# ATmega328.net
KiCad netlist of a schematic drawn in EAGLE
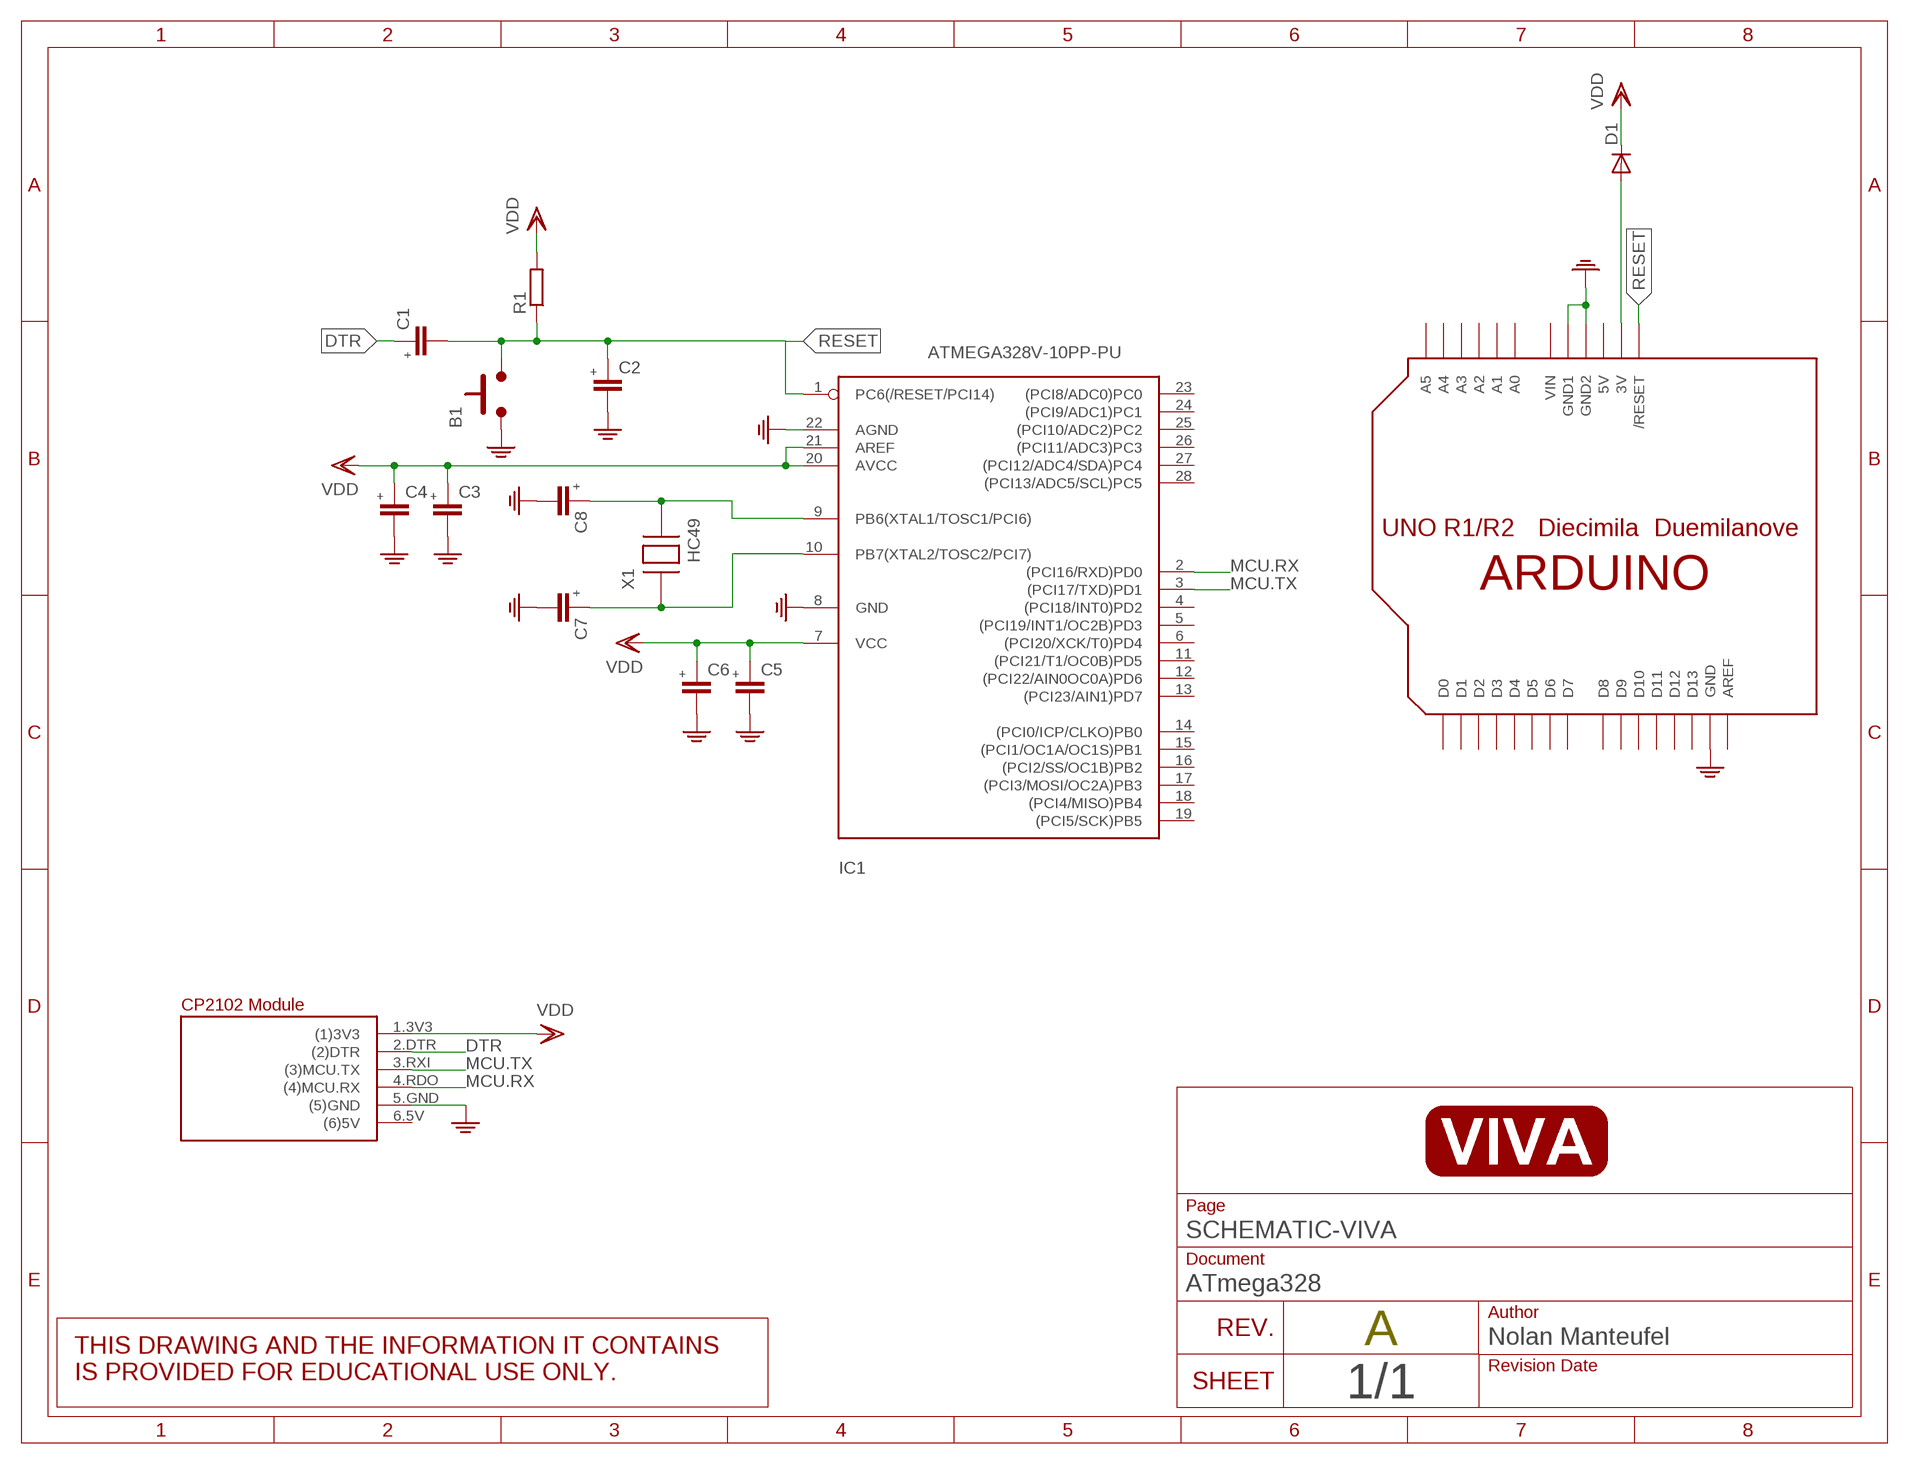
[diagram p0: schematic, sheet 1]

(export (version "E")
  (design (tool "Eeschema 10.0.6"))
  (components
    (comp (ref "B1")
      (value "PUSHBUTTON6X6MM")
      (footprint "eagle-import:6X6MM")
      (libsource (lib "eagle-import") (part "PUSHBUTTON6X6MM"))
    )
    (comp (ref "C1")
      (value "C-EUC0805")
      (footprint "eagle-import:C0805")
      (libsource (lib "eagle-import") (part "C-EUC0805"))
    )
    (comp (ref "C2")
      (value "C-EUC0805")
      (footprint "eagle-import:C0805")
      (libsource (lib "eagle-import") (part "C-EUC0805"))
    )
    (comp (ref "C3")
      (value "C-EUC0805")
      (footprint "eagle-import:C0805")
      (libsource (lib "eagle-import") (part "C-EUC0805"))
    )
    (comp (ref "C4")
      (value "C-EUC0805")
      (footprint "eagle-import:C0805")
      (libsource (lib "eagle-import") (part "C-EUC0805"))
    )
    (comp (ref "C5")
      (value "C-EUC0805")
      (footprint "eagle-import:C0805")
      (libsource (lib "eagle-import") (part "C-EUC0805"))
    )
    (comp (ref "C6")
      (value "C-EUC0805")
      (footprint "eagle-import:C0805")
      (libsource (lib "eagle-import") (part "C-EUC0805"))
    )
    (comp (ref "C7")
      (value "C-EUC0805")
      (footprint "eagle-import:C0805")
      (libsource (lib "eagle-import") (part "C-EUC0805"))
    )
    (comp (ref "C8")
      (value "C-EUC0805")
      (footprint "eagle-import:C0805")
      (libsource (lib "eagle-import") (part "C-EUC0805"))
    )
    (comp (ref "D1")
      (value "DIODE-SOD123")
      (footprint "eagle-import:SOD123")
      (libsource (lib "eagle-import") (part "DIODE-SOD123"))
    )
    (comp (ref "IC1")
      (value "ATMEGA328V-10PP-PU")
      (footprint "eagle-import:DIL28-3")
      (libsource (lib "eagle-import") (part "ATMEGA328PP-PUV-10"))
    )
    (comp (ref "R1")
      (value "R-EU_R0805")
      (footprint "eagle-import:R0805")
      (libsource (lib "eagle-import") (part "R-EU_R0805"))
    )
    (comp (ref "U$2")
      (value "ARDUINOUNO")
      (footprint "eagle-import:ARDUINO")
      (libsource (lib "eagle-import") (part "ARDUINOUNO"))
    )
    (comp (ref "U$3")
      (value "VIVA_USB-TTLTEXT")
      (footprint "eagle-import:VIVA_USB-TTL")
      (libsource (lib "eagle-import") (part "VIVA_USB-TTLTEXT"))
    )
    (comp (ref "X1")
      (value "HC49")
      (footprint "eagle-import:HC49S")
      (libsource (lib "eagle-import") (part "CRYSTAL-M"))
    )
  )
  (nets
    (net (code "1") (name "/5V") (class "Default")
      (node (ref "U$2") (pin "5V") (pinfunction "5V_5V") (pintype "power_in"))
    )
    (net (code "2") (name "/MCU.RX") (class "Default")
      (node (ref "IC1") (pin "2") (pinfunction "(PCI16/RXD)PD0_2") (pintype "bidirectional"))
      (node (ref "U$3") (pin "4.RDO") (pinfunction "(4)MCU.RX_4.RDO") (pintype "bidirectional"))
    )
    (net (code "3") (name "/MCU.TX") (class "Default")
      (node (ref "IC1") (pin "3") (pinfunction "(PCI17/TXD)PD1_3") (pintype "bidirectional"))
      (node (ref "U$3") (pin "3.RXI") (pinfunction "(3)MCU.TX_3.RXI") (pintype "bidirectional"))
    )
    (net (code "4") (name "/VIN") (class "Default")
      (node (ref "U$2") (pin "VIN") (pinfunction "VIN_VIN") (pintype "power_in"))
    )
    (net (code "5") (name "DTR") (class "Default")
      (node (ref "C1") (pin "1") (pinfunction "1_1") (pintype "passive"))
      (node (ref "U$3") (pin "2.DTR") (pinfunction "(2)DTR_2.DTR") (pintype "bidirectional"))
    )
    (net (code "6") (name "GND") (class "Default")
      (node (ref "B1") (pin "1.A") (pinfunction "1_1.A") (pintype "bidirectional"))
      (node (ref "B1") (pin "2.A") (pinfunction "1_2.A") (pintype "bidirectional"))
      (node (ref "C2") (pin "2") (pinfunction "2_2") (pintype "passive"))
      (node (ref "C3") (pin "2") (pinfunction "2_2") (pintype "passive"))
      (node (ref "C4") (pin "2") (pinfunction "2_2") (pintype "passive"))
      (node (ref "C5") (pin "2") (pinfunction "2_2") (pintype "passive"))
      (node (ref "C6") (pin "2") (pinfunction "2_2") (pintype "passive"))
      (node (ref "C7") (pin "2") (pinfunction "2_2") (pintype "passive"))
      (node (ref "C8") (pin "2") (pinfunction "2_2") (pintype "passive"))
      (node (ref "IC1") (pin "22") (pinfunction "AGND_22") (pintype "bidirectional"))
      (node (ref "IC1") (pin "8") (pinfunction "GND_8") (pintype "bidirectional"))
      (node (ref "U$2") (pin "GND") (pinfunction "GND_GND") (pintype "power_in"))
      (node (ref "U$2") (pin "GND1") (pinfunction "GND1_GND1") (pintype "power_in"))
      (node (ref "U$2") (pin "GND2") (pinfunction "GND2_GND2") (pintype "power_in"))
      (node (ref "U$3") (pin "5.GND") (pinfunction "(5)GND_5.GND") (pintype "bidirectional"))
    )
    (net (code "7") (name "Net-(D1-PadA)") (class "Default")
      (node (ref "D1") (pin "A") (pinfunction "A_A") (pintype "passive"))
      (node (ref "U$2") (pin "3V") (pinfunction "3V_3V") (pintype "power_in"))
    )
    (net (code "8") (name "Net-(IC1-PB6(XTAL1{slash}TOSC1{slash}PCI6))") (class "Default")
      (node (ref "C8") (pin "1") (pinfunction "1_1") (pintype "passive"))
      (node (ref "IC1") (pin "9") (pinfunction "PB6(XTAL1/TOSC1/PCI6)_9") (pintype "bidirectional"))
      (node (ref "X1") (pin "P$2") (pinfunction "P$2_P$2") (pintype "bidirectional"))
    )
    (net (code "9") (name "Net-(IC1-PB7(XTAL2{slash}TOSC2{slash}PCI7))") (class "Default")
      (node (ref "C7") (pin "1") (pinfunction "1_1") (pintype "passive"))
      (node (ref "IC1") (pin "10") (pinfunction "PB7(XTAL2/TOSC2/PCI7)_10") (pintype "bidirectional"))
      (node (ref "X1") (pin "P$1") (pinfunction "P$1_P$1") (pintype "bidirectional"))
    )
    (net (code "10") (name "RESET") (class "Default")
      (node (ref "B1") (pin "3.B") (pinfunction "2_3.B") (pintype "bidirectional"))
      (node (ref "B1") (pin "4.B") (pinfunction "2_4.B") (pintype "bidirectional"))
      (node (ref "C1") (pin "2") (pinfunction "2_2") (pintype "passive"))
      (node (ref "C2") (pin "1") (pinfunction "1_1") (pintype "passive"))
      (node (ref "IC1") (pin "1") (pinfunction "PC6(/RESET/PCI14)_1") (pintype "bidirectional"))
      (node (ref "R1") (pin "1") (pinfunction "1_1") (pintype "passive"))
      (node (ref "U$2") (pin "RESET") (pinfunction "/RESET_RESET") (pintype "bidirectional"))
    )
    (net (code "11") (name "VDD") (class "Default")
      (node (ref "C3") (pin "1") (pinfunction "1_1") (pintype "passive"))
      (node (ref "C4") (pin "1") (pinfunction "1_1") (pintype "passive"))
      (node (ref "C5") (pin "1") (pinfunction "1_1") (pintype "passive"))
      (node (ref "C6") (pin "1") (pinfunction "1_1") (pintype "passive"))
      (node (ref "D1") (pin "C") (pinfunction "C_C") (pintype "passive"))
      (node (ref "IC1") (pin "20") (pinfunction "AVCC_20") (pintype "bidirectional"))
      (node (ref "IC1") (pin "21") (pinfunction "AREF_21") (pintype "bidirectional"))
      (node (ref "IC1") (pin "7") (pinfunction "VCC_7") (pintype "bidirectional"))
      (node (ref "R1") (pin "2") (pinfunction "2_2") (pintype "passive"))
      (node (ref "U$3") (pin "1.3V3") (pinfunction "(1)3V3_1.3V3") (pintype "bidirectional"))
    )
    (net (code "12") (name "unconnected-(IC1-(PCI0{slash}ICP{slash}CLKO)PB0-Pad14)") (class "Default")
      (node (ref "IC1") (pin "14") (pinfunction "(PCI0/ICP/CLKO)PB0_14") (pintype "bidirectional"))
    )
    (net (code "13") (name "unconnected-(IC1-(PCI1{slash}OC1A{slash}OC1S)PB1-Pad15)") (class "Default")
      (node (ref "IC1") (pin "15") (pinfunction "(PCI1/OC1A/OC1S)PB1_15") (pintype "bidirectional"))
    )
    (net (code "14") (name "unconnected-(IC1-(PCI2{slash}SS{slash}OC1B)PB2-Pad16)") (class "Default")
      (node (ref "IC1") (pin "16") (pinfunction "(PCI2/SS/OC1B)PB2_16") (pintype "bidirectional"))
    )
    (net (code "15") (name "unconnected-(IC1-(PCI3{slash}MOSI{slash}OC2A)PB3-Pad17)") (class "Default")
      (node (ref "IC1") (pin "17") (pinfunction "(PCI3/MOSI/OC2A)PB3_17") (pintype "bidirectional"))
    )
    (net (code "16") (name "unconnected-(IC1-(PCI4{slash}MISO)PB4-Pad18)") (class "Default")
      (node (ref "IC1") (pin "18") (pinfunction "(PCI4/MISO)PB4_18") (pintype "bidirectional"))
    )
    (net (code "17") (name "unconnected-(IC1-(PCI5{slash}SCK)PB5-Pad19)") (class "Default")
      (node (ref "IC1") (pin "19") (pinfunction "(PCI5/SCK)PB5_19") (pintype "bidirectional"))
    )
    (net (code "18") (name "unconnected-(IC1-(PCI8{slash}ADC0)PC0-Pad23)") (class "Default")
      (node (ref "IC1") (pin "23") (pinfunction "(PCI8/ADC0)PC0_23") (pintype "bidirectional"))
    )
    (net (code "19") (name "unconnected-(IC1-(PCI9{slash}ADC1)PC1-Pad24)") (class "Default")
      (node (ref "IC1") (pin "24") (pinfunction "(PCI9/ADC1)PC1_24") (pintype "bidirectional"))
    )
    (net (code "20") (name "unconnected-(IC1-(PCI10{slash}ADC2)PC2-Pad25)") (class "Default")
      (node (ref "IC1") (pin "25") (pinfunction "(PCI10/ADC2)PC2_25") (pintype "bidirectional"))
    )
    (net (code "21") (name "unconnected-(IC1-(PCI11{slash}ADC3)PC3-Pad26)") (class "Default")
      (node (ref "IC1") (pin "26") (pinfunction "(PCI11/ADC3)PC3_26") (pintype "bidirectional"))
    )
    (net (code "22") (name "unconnected-(IC1-(PCI12{slash}ADC4{slash}SDA)PC4-Pad27)") (class "Default")
      (node (ref "IC1") (pin "27") (pinfunction "(PCI12/ADC4/SDA)PC4_27") (pintype "bidirectional"))
    )
    (net (code "23") (name "unconnected-(IC1-(PCI13{slash}ADC5{slash}SCL)PC5-Pad28)") (class "Default")
      (node (ref "IC1") (pin "28") (pinfunction "(PCI13/ADC5/SCL)PC5_28") (pintype "bidirectional"))
    )
    (net (code "24") (name "unconnected-(IC1-(PCI18{slash}INT0)PD2-Pad4)") (class "Default")
      (node (ref "IC1") (pin "4") (pinfunction "(PCI18/INT0)PD2_4") (pintype "bidirectional"))
    )
    (net (code "25") (name "unconnected-(IC1-(PCI19{slash}INT1{slash}OC2B)PD3-Pad5)") (class "Default")
      (node (ref "IC1") (pin "5") (pinfunction "(PCI19/INT1/OC2B)PD3_5") (pintype "bidirectional"))
    )
    (net (code "26") (name "unconnected-(IC1-(PCI20{slash}XCK{slash}T0)PD4-Pad6)") (class "Default")
      (node (ref "IC1") (pin "6") (pinfunction "(PCI20/XCK/T0)PD4_6") (pintype "bidirectional"))
    )
    (net (code "27") (name "unconnected-(IC1-(PCI21{slash}T1{slash}OC0B)PD5-Pad11)") (class "Default")
      (node (ref "IC1") (pin "11") (pinfunction "(PCI21/T1/OC0B)PD5_11") (pintype "bidirectional"))
    )
    (net (code "28") (name "unconnected-(IC1-(PCI22{slash}AIN0OC0A)PD6-Pad12)") (class "Default")
      (node (ref "IC1") (pin "12") (pinfunction "(PCI22/AIN0OC0A)PD6_12") (pintype "bidirectional"))
    )
    (net (code "29") (name "unconnected-(IC1-(PCI23{slash}AIN1)PD7-Pad13)") (class "Default")
      (node (ref "IC1") (pin "13") (pinfunction "(PCI23/AIN1)PD7_13") (pintype "bidirectional"))
    )
    (net (code "30") (name "unconnected-(U$2-PadA0)") (class "Default")
      (node (ref "U$2") (pin "A0") (pinfunction "A0_A0") (pintype "bidirectional"))
    )
    (net (code "31") (name "unconnected-(U$2-PadA1)") (class "Default")
      (node (ref "U$2") (pin "A1") (pinfunction "A1_A1") (pintype "bidirectional"))
    )
    (net (code "32") (name "unconnected-(U$2-PadA2)") (class "Default")
      (node (ref "U$2") (pin "A2") (pinfunction "A2_A2") (pintype "bidirectional"))
    )
    (net (code "33") (name "unconnected-(U$2-PadA3)") (class "Default")
      (node (ref "U$2") (pin "A3") (pinfunction "A3_A3") (pintype "bidirectional"))
    )
    (net (code "34") (name "unconnected-(U$2-PadA4)") (class "Default")
      (node (ref "U$2") (pin "A4") (pinfunction "A4_A4") (pintype "bidirectional"))
    )
    (net (code "35") (name "unconnected-(U$2-PadA5)") (class "Default")
      (node (ref "U$2") (pin "A5") (pinfunction "A5_A5") (pintype "bidirectional"))
    )
    (net (code "36") (name "unconnected-(U$2-PadAREF)") (class "Default")
      (node (ref "U$2") (pin "AREF") (pinfunction "AREF_AREF") (pintype "bidirectional"))
    )
    (net (code "37") (name "unconnected-(U$2-PadD0)") (class "Default")
      (node (ref "U$2") (pin "D0") (pinfunction "D0_D0") (pintype "bidirectional"))
    )
    (net (code "38") (name "unconnected-(U$2-PadD1)") (class "Default")
      (node (ref "U$2") (pin "D1") (pinfunction "D1_D1") (pintype "bidirectional"))
    )
    (net (code "39") (name "unconnected-(U$2-PadD2)") (class "Default")
      (node (ref "U$2") (pin "D2") (pinfunction "D2_D2") (pintype "bidirectional"))
    )
    (net (code "40") (name "unconnected-(U$2-PadD3)") (class "Default")
      (node (ref "U$2") (pin "D3") (pinfunction "D3_D3") (pintype "bidirectional"))
    )
    (net (code "41") (name "unconnected-(U$2-PadD4)") (class "Default")
      (node (ref "U$2") (pin "D4") (pinfunction "D4_D4") (pintype "bidirectional"))
    )
    (net (code "42") (name "unconnected-(U$2-PadD5)") (class "Default")
      (node (ref "U$2") (pin "D5") (pinfunction "D5_D5") (pintype "bidirectional"))
    )
    (net (code "43") (name "unconnected-(U$2-PadD6)") (class "Default")
      (node (ref "U$2") (pin "D6") (pinfunction "D6_D6") (pintype "bidirectional"))
    )
    (net (code "44") (name "unconnected-(U$2-PadD7)") (class "Default")
      (node (ref "U$2") (pin "D7") (pinfunction "D7_D7") (pintype "bidirectional"))
    )
    (net (code "45") (name "unconnected-(U$2-PadD8)") (class "Default")
      (node (ref "U$2") (pin "D8") (pinfunction "D8_D8") (pintype "bidirectional"))
    )
    (net (code "46") (name "unconnected-(U$2-PadD9)") (class "Default")
      (node (ref "U$2") (pin "D9") (pinfunction "D9_D9") (pintype "bidirectional"))
    )
    (net (code "47") (name "unconnected-(U$2-PadD10)") (class "Default")
      (node (ref "U$2") (pin "D10") (pinfunction "D10_D10") (pintype "bidirectional"))
    )
    (net (code "48") (name "unconnected-(U$2-PadD11)") (class "Default")
      (node (ref "U$2") (pin "D11") (pinfunction "D11_D11") (pintype "bidirectional"))
    )
    (net (code "49") (name "unconnected-(U$2-PadD12)") (class "Default")
      (node (ref "U$2") (pin "D12") (pinfunction "D12_D12") (pintype "bidirectional"))
    )
    (net (code "50") (name "unconnected-(U$2-PadD13)") (class "Default")
      (node (ref "U$2") (pin "D13") (pinfunction "D13_D13") (pintype "bidirectional"))
    )
    (net (code "51") (name "unconnected-(U$3-(6)5V-Pad6.5V)") (class "Default")
      (node (ref "U$3") (pin "6.5V") (pinfunction "(6)5V_6.5V") (pintype "bidirectional"))
    )
  )
)
